# Driver4.net
KiCad netlist of a schematic drawn in Altium Designer
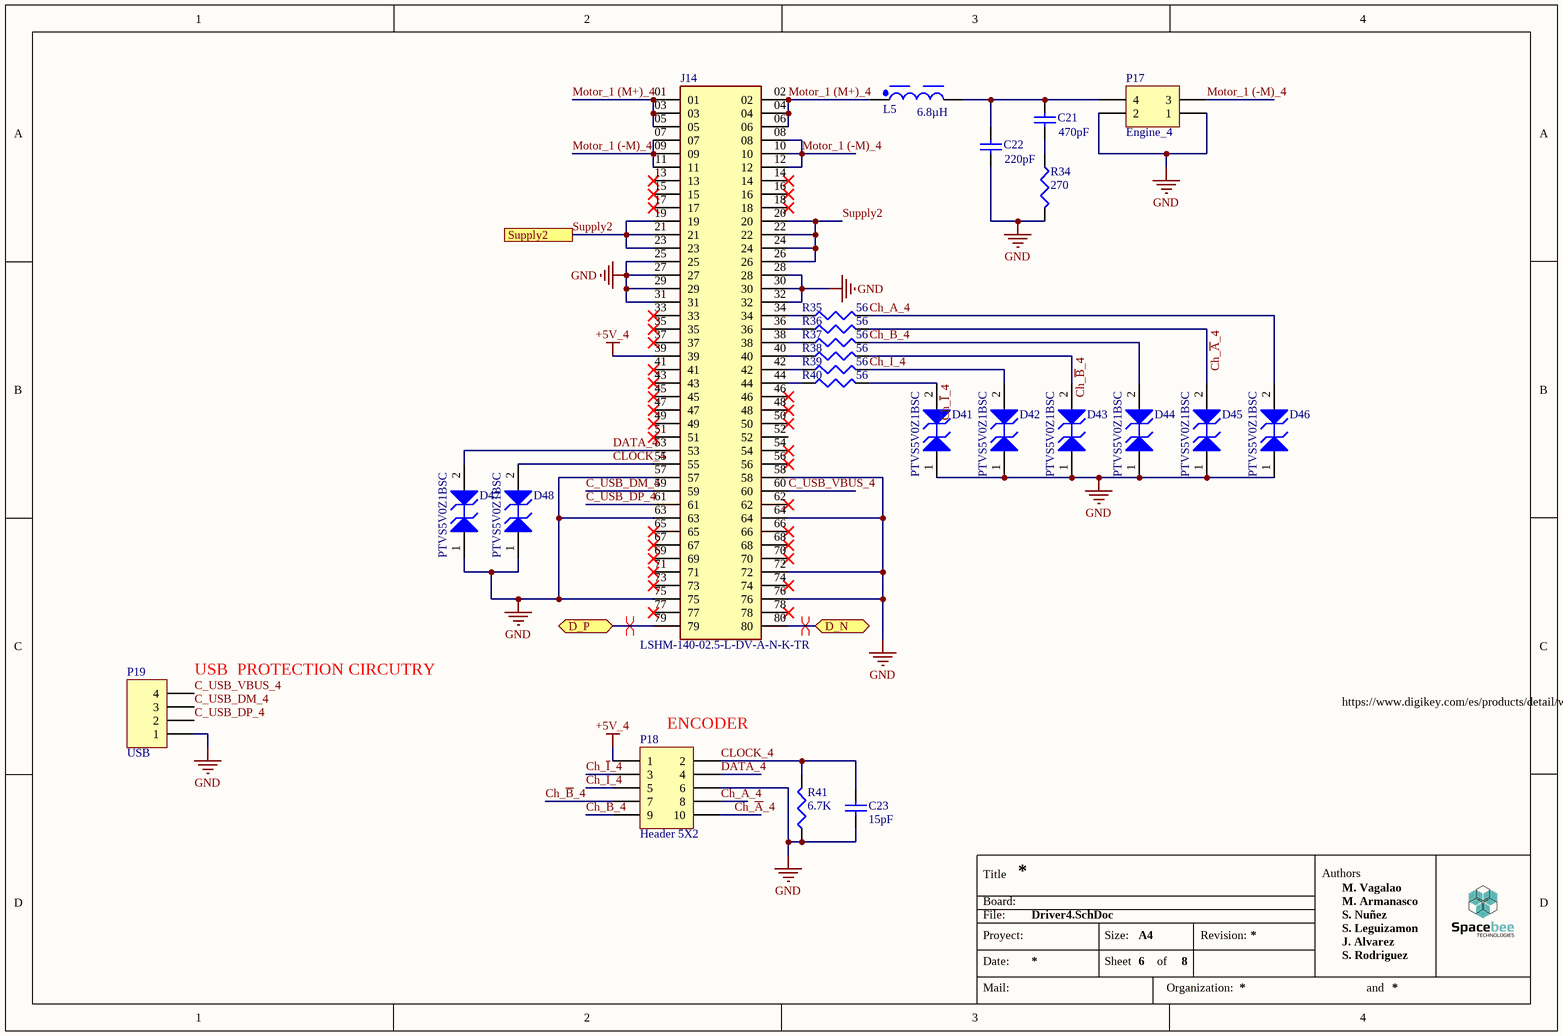
[diagram p0: Driver4.SchDoc]

(export (version "E")
  (design (tool "Eeschema 10.0.6"))
  (components
    (comp (ref "C21")
      (value "470pF")
      (footprint "1608[0603]")
      (description "Capacitor (Semiconductor SIM Model)")
      (fields (field (name "Comment") "Cap Semi") (field (name "PUBLISHER") "Altium Limited"))
      (libsource (lib "Miscellaneous Devices") (part "Cap Semi"))
    )
    (comp (ref "C22")
      (value "220pF")
      (footprint "1608[0603]")
      (description "Capacitor (Semiconductor SIM Model)")
      (fields (field (name "Comment") "Cap Semi") (field (name "PUBLISHER") "Altium Limited"))
      (libsource (lib "Miscellaneous Devices") (part "Cap Semi"))
    )
    (comp (ref "C23")
      (value "15pF")
      (footprint "6-0805_L")
      (description "Capacitor (Semiconductor SIM Model)")
      (fields (field (name "Comment") "Cap Semi") (field (name "PUBLISHER") "Altium Limited"))
      (libsource (lib "SpaceBee") (part "Cap 0805"))
    )
    (comp (ref "D41")
      (value "PTVS5V0Z1BSC")
      (footprint "SOD993B")
      (fields (field (name "MANUFACTURER") "On Semiconductor") (field (name "PARTNUMBER") "1SMB16CAT3"))
      (libsource (lib "DriverLib") (part "PTVS5V0Z1BSC"))
    )
    (comp (ref "D42")
      (value "PTVS5V0Z1BSC")
      (footprint "SOD993B")
      (fields (field (name "MANUFACTURER") "On Semiconductor") (field (name "PARTNUMBER") "1SMB16CAT3"))
      (libsource (lib "DriverLib") (part "PTVS5V0Z1BSC"))
    )
    (comp (ref "D43")
      (value "PTVS5V0Z1BSC")
      (footprint "SOD993B")
      (fields (field (name "MANUFACTURER") "On Semiconductor") (field (name "PARTNUMBER") "1SMB16CAT3"))
      (libsource (lib "DriverLib") (part "PTVS5V0Z1BSC"))
    )
    (comp (ref "D44")
      (value "PTVS5V0Z1BSC")
      (footprint "SOD993B")
      (fields (field (name "MANUFACTURER") "On Semiconductor") (field (name "PARTNUMBER") "1SMB16CAT3"))
      (libsource (lib "DriverLib") (part "PTVS5V0Z1BSC"))
    )
    (comp (ref "D45")
      (value "PTVS5V0Z1BSC")
      (footprint "SOD993B")
      (fields (field (name "MANUFACTURER") "On Semiconductor") (field (name "PARTNUMBER") "1SMB16CAT3"))
      (libsource (lib "DriverLib") (part "PTVS5V0Z1BSC"))
    )
    (comp (ref "D46")
      (value "PTVS5V0Z1BSC")
      (footprint "SOD993B")
      (fields (field (name "MANUFACTURER") "On Semiconductor") (field (name "PARTNUMBER") "1SMB16CAT3"))
      (libsource (lib "DriverLib") (part "PTVS5V0Z1BSC"))
    )
    (comp (ref "D47")
      (value "PTVS5V0Z1BSC")
      (footprint "SOD993B")
      (fields (field (name "MANUFACTURER") "On Semiconductor") (field (name "PARTNUMBER") "1SMB16CAT3"))
      (libsource (lib "DriverLib") (part "PTVS5V0Z1BSC"))
    )
    (comp (ref "D48")
      (value "PTVS5V0Z1BSC")
      (footprint "SOD993B")
      (fields (field (name "MANUFACTURER") "On Semiconductor") (field (name "PARTNUMBER") "1SMB16CAT3"))
      (libsource (lib "DriverLib") (part "PTVS5V0Z1BSC"))
    )
    (comp (ref "J14")
      (value "LSHM-140-02.5-L-DV-A-N-K-TR")
      (footprint "SAMTEC_LSHM-140-02.5-L-DV-A-N-K-TR")
      (description "LSHM - Samtec 0.50mm Razor Beam High-Speed Hermaphroditic Terminal / Socket Strip.")
      (libsource (lib "DriverLib") (part "LSHM-140-02.5-L-DV-A-N-K-TR"))
    )
    (comp (ref "L5")
      (value "6.8µH")
      (footprint "WE-XHMA_6060")
      (description "WE-XHMA SMD Power Inductor, size 1090, 6.8µH, 10.5A, 7.16mΩ")
      (fields
        (field (name "MANUFACTURER PART NUMBER") "78439369068")
        (field (name "MANUFACTURER") "Wurth Elektronik")
      )
      (libsource (lib "DriverLib") (part "78439369068"))
    )
    (comp (ref "P17")
      (value "Engine_4")
      (footprint "MOLEX_1724480004")
      (description "Header, 2-Pin, Dual row")
      (fields (field (name "PUBLISHER") "Altium Limited"))
      (libsource (lib "SpaceBee") (part "Header 2X2"))
    )
    (comp (ref "P18")
      (value "Header 5X2")
      (footprint "CONN_HIF3FC-14PA-2.54DS(71)_HIR")
      (description "Header, 5-Pin, Dual row")
      (fields (field (name "PUBLISHER") "Altium Limited"))
      (libsource (lib "DriverLib") (part "Header 5X2"))
    )
    (comp (ref "P19")
      (value "USB")
      (footprint "Header 4 SMD")
      (description "Header, 4-Pin")
      (fields (field (name "PUBLISHER") "Altium Limited"))
      (libsource (lib "SpaceBee") (part "Header 4 SMD"))
    )
    (comp (ref "R34")
      (value "270")
      (footprint "J1-0603")
      (description "Resistor")
      (fields (field (name "Comment") "Res3") (field (name "PUBLISHER") "Altium Limited"))
      (libsource (lib "Miscellaneous Devices") (part "Res3"))
    )
    (comp (ref "R35")
      (value "56")
      (footprint "J1-0603")
      (description "Resistor")
      (fields (field (name "Comment") "Res3") (field (name "PUBLISHER") "Altium Limited"))
      (libsource (lib "Miscellaneous Devices") (part "Res3"))
    )
    (comp (ref "R36")
      (value "56")
      (footprint "J1-0603")
      (description "Resistor")
      (fields (field (name "Comment") "Res3") (field (name "PUBLISHER") "Altium Limited"))
      (libsource (lib "Miscellaneous Devices") (part "Res3"))
    )
    (comp (ref "R37")
      (value "56")
      (footprint "J1-0603")
      (description "Resistor")
      (fields (field (name "Comment") "Res3") (field (name "PUBLISHER") "Altium Limited"))
      (libsource (lib "Miscellaneous Devices") (part "Res3"))
    )
    (comp (ref "R38")
      (value "56")
      (footprint "J1-0603")
      (description "Resistor")
      (fields (field (name "Comment") "Res3") (field (name "PUBLISHER") "Altium Limited"))
      (libsource (lib "Miscellaneous Devices") (part "Res3"))
    )
    (comp (ref "R39")
      (value "56")
      (footprint "J1-0603")
      (description "Resistor")
      (fields (field (name "Comment") "Res3") (field (name "PUBLISHER") "Altium Limited"))
      (libsource (lib "Miscellaneous Devices") (part "Res3"))
    )
    (comp (ref "R40")
      (value "56")
      (footprint "J1-0603")
      (description "Resistor")
      (fields (field (name "Comment") "Res3") (field (name "PUBLISHER") "Altium Limited"))
      (libsource (lib "Miscellaneous Devices") (part "Res3"))
    )
    (comp (ref "R41")
      (value "6.7K")
      (footprint "J1-0603")
      (description "Resistor")
      (fields (field (name "Comment") "Res3") (field (name "PUBLISHER") "Altium Limited"))
      (libsource (lib "Miscellaneous Devices") (part "Res3"))
    )
  )
  (nets
    (net (code "1") (name "+5V_4") (class "Default")
      (node (ref "J14") (pin "39") (pinfunction "39_39") (pintype "passive"))
      (node (ref "P18") (pin "1") (pinfunction "1_1") (pintype "passive"))
    )
    (net (code "2") (name "/CLOCK_4") (class "Default")
      (node (ref "C23") (pin "2") (pinfunction "2_2") (pintype "passive"))
      (node (ref "D48") (pin "2") (pinfunction "A2_2") (pintype "passive"))
      (node (ref "J14") (pin "55") (pinfunction "55_55") (pintype "passive"))
      (node (ref "P18") (pin "2") (pinfunction "2_2") (pintype "passive"))
      (node (ref "R41") (pin "2") (pinfunction "2_2") (pintype "passive"))
    )
    (net (code "3") (name "/C_USB_DM_4") (class "Default")
      (node (ref "J14") (pin "59") (pinfunction "59_59") (pintype "passive"))
      (node (ref "P19") (pin "3") (pinfunction "3_3") (pintype "passive"))
    )
    (net (code "4") (name "/C_USB_DP_4") (class "Default")
      (node (ref "J14") (pin "61") (pinfunction "61_61") (pintype "passive"))
      (node (ref "P19") (pin "2") (pinfunction "2_2") (pintype "passive"))
    )
    (net (code "5") (name "/C_USB_VBUS_4") (class "Default")
      (node (ref "J14") (pin "60") (pinfunction "60_60") (pintype "passive"))
      (node (ref "P19") (pin "4") (pinfunction "4_4") (pintype "passive"))
    )
    (net (code "6") (name "/Ch_A_4") (class "Default")
      (node (ref "D46") (pin "2") (pinfunction "A2_2") (pintype "passive"))
      (node (ref "P18") (pin "8") (pinfunction "8_8") (pintype "passive"))
      (node (ref "R35") (pin "2") (pinfunction "2_2") (pintype "passive"))
    )
    (net (code "7") (name "/Ch_B_4") (class "Default")
      (node (ref "D44") (pin "2") (pinfunction "A2_2") (pintype "passive"))
      (node (ref "P18") (pin "9") (pinfunction "9_9") (pintype "passive"))
      (node (ref "R37") (pin "2") (pinfunction "2_2") (pintype "passive"))
    )
    (net (code "8") (name "/Ch_I_4") (class "Default")
      (node (ref "D42") (pin "2") (pinfunction "A2_2") (pintype "passive"))
      (node (ref "P18") (pin "5") (pinfunction "5_5") (pintype "passive"))
      (node (ref "R39") (pin "2") (pinfunction "2_2") (pintype "passive"))
    )
    (net (code "9") (name "/Ch_~{A}_4") (class "Default")
      (node (ref "D45") (pin "2") (pinfunction "A2_2") (pintype "passive"))
      (node (ref "P18") (pin "10") (pinfunction "10_10") (pintype "passive"))
      (node (ref "R36") (pin "2") (pinfunction "2_2") (pintype "passive"))
    )
    (net (code "10") (name "/Ch_~{B}_4") (class "Default")
      (node (ref "D43") (pin "2") (pinfunction "A2_2") (pintype "passive"))
      (node (ref "P18") (pin "7") (pinfunction "7_7") (pintype "passive"))
      (node (ref "R38") (pin "2") (pinfunction "2_2") (pintype "passive"))
    )
    (net (code "11") (name "/Ch_~{I}_4") (class "Default")
      (node (ref "D41") (pin "2") (pinfunction "A2_2") (pintype "passive"))
      (node (ref "P18") (pin "3") (pinfunction "3_3") (pintype "passive"))
      (node (ref "R40") (pin "2") (pinfunction "2_2") (pintype "passive"))
    )
    (net (code "12") (name "/DATA_4") (class "Default")
      (node (ref "D47") (pin "2") (pinfunction "A2_2") (pintype "passive"))
      (node (ref "J14") (pin "53") (pinfunction "53_53") (pintype "passive"))
      (node (ref "P18") (pin "4") (pinfunction "4_4") (pintype "passive"))
    )
    (net (code "13") (name "/D_N") (class "Default")
      (node (ref "J14") (pin "80") (pinfunction "80_80") (pintype "passive"))
    )
    (net (code "14") (name "/D_P") (class "Default")
      (node (ref "J14") (pin "79") (pinfunction "79_79") (pintype "passive"))
    )
    (net (code "15") (name "/Motor_1 (-M)_4") (class "Default")
      (node (ref "J14") (pin "07") (pinfunction "07_07") (pintype "passive"))
      (node (ref "J14") (pin "08") (pinfunction "08_08") (pintype "passive"))
      (node (ref "J14") (pin "09") (pinfunction "09_09") (pintype "passive"))
      (node (ref "J14") (pin "10") (pinfunction "10_10") (pintype "passive"))
      (node (ref "J14") (pin "11") (pinfunction "11_11") (pintype "passive"))
      (node (ref "J14") (pin "12") (pinfunction "12_12") (pintype "passive"))
      (node (ref "P17") (pin "3") (pinfunction "3_3") (pintype "passive"))
    )
    (net (code "16") (name "/Motor_1 (M+)_4") (class "Default")
      (node (ref "J14") (pin "01") (pinfunction "01_01") (pintype "passive"))
      (node (ref "J14") (pin "02") (pinfunction "02_02") (pintype "passive"))
      (node (ref "J14") (pin "03") (pinfunction "03_03") (pintype "passive"))
      (node (ref "J14") (pin "04") (pinfunction "04_04") (pintype "passive"))
      (node (ref "J14") (pin "05") (pinfunction "05_05") (pintype "passive"))
      (node (ref "J14") (pin "06") (pinfunction "06_06") (pintype "passive"))
      (node (ref "L5") (pin "1") (pinfunction "1_1") (pintype "passive"))
    )
    (net (code "17") (name "/Supply2") (class "Default")
      (node (ref "J14") (pin "19") (pinfunction "19_19") (pintype "passive"))
      (node (ref "J14") (pin "20") (pinfunction "20_20") (pintype "passive"))
      (node (ref "J14") (pin "21") (pinfunction "21_21") (pintype "passive"))
      (node (ref "J14") (pin "22") (pinfunction "22_22") (pintype "passive"))
      (node (ref "J14") (pin "23") (pinfunction "23_23") (pintype "passive"))
      (node (ref "J14") (pin "24") (pinfunction "24_24") (pintype "passive"))
      (node (ref "J14") (pin "26") (pinfunction "26_26") (pintype "passive"))
    )
    (net (code "18") (name "GND") (class "Default")
      (node (ref "C22") (pin "2") (pinfunction "2_2") (pintype "passive"))
      (node (ref "C23") (pin "1") (pinfunction "1_1") (pintype "passive"))
      (node (ref "D41") (pin "1") (pinfunction "A1_1") (pintype "passive"))
      (node (ref "D42") (pin "1") (pinfunction "A1_1") (pintype "passive"))
      (node (ref "D43") (pin "1") (pinfunction "A1_1") (pintype "passive"))
      (node (ref "D44") (pin "1") (pinfunction "A1_1") (pintype "passive"))
      (node (ref "D45") (pin "1") (pinfunction "A1_1") (pintype "passive"))
      (node (ref "D46") (pin "1") (pinfunction "A1_1") (pintype "passive"))
      (node (ref "D47") (pin "1") (pinfunction "A1_1") (pintype "passive"))
      (node (ref "D48") (pin "1") (pinfunction "A1_1") (pintype "passive"))
      (node (ref "J14") (pin "25") (pinfunction "25_25") (pintype "passive"))
      (node (ref "J14") (pin "27") (pinfunction "27_27") (pintype "passive"))
      (node (ref "J14") (pin "28") (pinfunction "28_28") (pintype "passive"))
      (node (ref "J14") (pin "29") (pinfunction "29_29") (pintype "passive"))
      (node (ref "J14") (pin "30") (pinfunction "30_30") (pintype "passive"))
      (node (ref "J14") (pin "31") (pinfunction "31_31") (pintype "passive"))
      (node (ref "J14") (pin "32") (pinfunction "32_32") (pintype "passive"))
      (node (ref "J14") (pin "57") (pinfunction "57_57") (pintype "passive"))
      (node (ref "J14") (pin "58") (pinfunction "58_58") (pintype "passive"))
      (node (ref "J14") (pin "63") (pinfunction "63_63") (pintype "passive"))
      (node (ref "J14") (pin "64") (pinfunction "64_64") (pintype "passive"))
      (node (ref "J14") (pin "72") (pinfunction "72_72") (pintype "passive"))
      (node (ref "J14") (pin "75") (pinfunction "75_75") (pintype "passive"))
      (node (ref "J14") (pin "76") (pinfunction "76_76") (pintype "passive"))
      (node (ref "P17") (pin "1") (pinfunction "1_1") (pintype "passive"))
      (node (ref "P17") (pin "2") (pinfunction "2_2") (pintype "passive"))
      (node (ref "P18") (pin "6") (pinfunction "6_6") (pintype "passive"))
      (node (ref "P19") (pin "1") (pinfunction "1_1") (pintype "passive"))
      (node (ref "R34") (pin "2") (pinfunction "2_2") (pintype "passive"))
      (node (ref "R41") (pin "1") (pinfunction "1_1") (pintype "passive"))
    )
    (net (code "19") (name "Net-(C21-Pad1)") (class "Default")
      (node (ref "C21") (pin "1") (pinfunction "1_1") (pintype "passive"))
      (node (ref "C22") (pin "1") (pinfunction "1_1") (pintype "passive"))
      (node (ref "L5") (pin "2") (pinfunction "2_2") (pintype "passive"))
      (node (ref "P17") (pin "4") (pinfunction "4_4") (pintype "passive"))
    )
    (net (code "20") (name "Net-(C21-Pad2)") (class "Default")
      (node (ref "C21") (pin "2") (pinfunction "2_2") (pintype "passive"))
      (node (ref "R34") (pin "1") (pinfunction "1_1") (pintype "passive"))
    )
    (net (code "21") (name "Net-(J14-Pad34)") (class "Default")
      (node (ref "J14") (pin "34") (pinfunction "34_34") (pintype "passive"))
      (node (ref "R35") (pin "1") (pinfunction "1_1") (pintype "passive"))
    )
    (net (code "22") (name "Net-(J14-Pad36)") (class "Default")
      (node (ref "J14") (pin "36") (pinfunction "36_36") (pintype "passive"))
      (node (ref "R36") (pin "1") (pinfunction "1_1") (pintype "passive"))
    )
    (net (code "23") (name "Net-(J14-Pad38)") (class "Default")
      (node (ref "J14") (pin "38") (pinfunction "38_38") (pintype "passive"))
      (node (ref "R37") (pin "1") (pinfunction "1_1") (pintype "passive"))
    )
    (net (code "24") (name "Net-(J14-Pad40)") (class "Default")
      (node (ref "J14") (pin "40") (pinfunction "40_40") (pintype "passive"))
      (node (ref "R38") (pin "1") (pinfunction "1_1") (pintype "passive"))
    )
    (net (code "25") (name "Net-(J14-Pad42)") (class "Default")
      (node (ref "J14") (pin "42") (pinfunction "42_42") (pintype "passive"))
      (node (ref "R39") (pin "1") (pinfunction "1_1") (pintype "passive"))
    )
    (net (code "26") (name "Net-(J14-Pad44)") (class "Default")
      (node (ref "J14") (pin "44") (pinfunction "44_44") (pintype "passive"))
      (node (ref "R40") (pin "1") (pinfunction "1_1") (pintype "passive"))
    )
    (net (code "27") (name "unconnected-(J14-Pad13)") (class "Default")
      (node (ref "J14") (pin "13") (pinfunction "13_13") (pintype "passive+no_connect"))
    )
    (net (code "28") (name "unconnected-(J14-Pad14)") (class "Default")
      (node (ref "J14") (pin "14") (pinfunction "14_14") (pintype "passive+no_connect"))
    )
    (net (code "29") (name "unconnected-(J14-Pad15)") (class "Default")
      (node (ref "J14") (pin "15") (pinfunction "15_15") (pintype "passive+no_connect"))
    )
    (net (code "30") (name "unconnected-(J14-Pad16)") (class "Default")
      (node (ref "J14") (pin "16") (pinfunction "16_16") (pintype "passive+no_connect"))
    )
    (net (code "31") (name "unconnected-(J14-Pad17)") (class "Default")
      (node (ref "J14") (pin "17") (pinfunction "17_17") (pintype "passive+no_connect"))
    )
    (net (code "32") (name "unconnected-(J14-Pad18)") (class "Default")
      (node (ref "J14") (pin "18") (pinfunction "18_18") (pintype "passive+no_connect"))
    )
    (net (code "33") (name "unconnected-(J14-Pad33)") (class "Default")
      (node (ref "J14") (pin "33") (pinfunction "33_33") (pintype "passive+no_connect"))
    )
    (net (code "34") (name "unconnected-(J14-Pad35)") (class "Default")
      (node (ref "J14") (pin "35") (pinfunction "35_35") (pintype "passive+no_connect"))
    )
    (net (code "35") (name "unconnected-(J14-Pad37)") (class "Default")
      (node (ref "J14") (pin "37") (pinfunction "37_37") (pintype "passive+no_connect"))
    )
    (net (code "36") (name "unconnected-(J14-Pad41)") (class "Default")
      (node (ref "J14") (pin "41") (pinfunction "41_41") (pintype "passive+no_connect"))
    )
    (net (code "37") (name "unconnected-(J14-Pad43)") (class "Default")
      (node (ref "J14") (pin "43") (pinfunction "43_43") (pintype "passive+no_connect"))
    )
    (net (code "38") (name "unconnected-(J14-Pad45)") (class "Default")
      (node (ref "J14") (pin "45") (pinfunction "45_45") (pintype "passive+no_connect"))
    )
    (net (code "39") (name "unconnected-(J14-Pad46)") (class "Default")
      (node (ref "J14") (pin "46") (pinfunction "46_46") (pintype "passive+no_connect"))
    )
    (net (code "40") (name "unconnected-(J14-Pad47)") (class "Default")
      (node (ref "J14") (pin "47") (pinfunction "47_47") (pintype "passive+no_connect"))
    )
    (net (code "41") (name "unconnected-(J14-Pad48)") (class "Default")
      (node (ref "J14") (pin "48") (pinfunction "48_48") (pintype "passive+no_connect"))
    )
    (net (code "42") (name "unconnected-(J14-Pad49)") (class "Default")
      (node (ref "J14") (pin "49") (pinfunction "49_49") (pintype "passive+no_connect"))
    )
    (net (code "43") (name "unconnected-(J14-Pad50)") (class "Default")
      (node (ref "J14") (pin "50") (pinfunction "50_50") (pintype "passive+no_connect"))
    )
    (net (code "44") (name "unconnected-(J14-Pad51)") (class "Default")
      (node (ref "J14") (pin "51") (pinfunction "51_51") (pintype "passive+no_connect"))
    )
    (net (code "45") (name "unconnected-(J14-Pad52)") (class "Default")
      (node (ref "J14") (pin "52") (pinfunction "52_52") (pintype "passive"))
    )
    (net (code "46") (name "unconnected-(J14-Pad54)") (class "Default")
      (node (ref "J14") (pin "54") (pinfunction "54_54") (pintype "passive+no_connect"))
    )
    (net (code "47") (name "unconnected-(J14-Pad56)") (class "Default")
      (node (ref "J14") (pin "56") (pinfunction "56_56") (pintype "passive+no_connect"))
    )
    (net (code "48") (name "unconnected-(J14-Pad62)") (class "Default")
      (node (ref "J14") (pin "62") (pinfunction "62_62") (pintype "passive+no_connect"))
    )
    (net (code "49") (name "unconnected-(J14-Pad65)") (class "Default")
      (node (ref "J14") (pin "65") (pinfunction "65_65") (pintype "passive+no_connect"))
    )
    (net (code "50") (name "unconnected-(J14-Pad66)") (class "Default")
      (node (ref "J14") (pin "66") (pinfunction "66_66") (pintype "passive+no_connect"))
    )
    (net (code "51") (name "unconnected-(J14-Pad67)") (class "Default")
      (node (ref "J14") (pin "67") (pinfunction "67_67") (pintype "passive+no_connect"))
    )
    (net (code "52") (name "unconnected-(J14-Pad68)") (class "Default")
      (node (ref "J14") (pin "68") (pinfunction "68_68") (pintype "passive+no_connect"))
    )
    (net (code "53") (name "unconnected-(J14-Pad69)") (class "Default")
      (node (ref "J14") (pin "69") (pinfunction "69_69") (pintype "passive+no_connect"))
    )
    (net (code "54") (name "unconnected-(J14-Pad70)") (class "Default")
      (node (ref "J14") (pin "70") (pinfunction "70_70") (pintype "passive+no_connect"))
    )
    (net (code "55") (name "unconnected-(J14-Pad71)") (class "Default")
      (node (ref "J14") (pin "71") (pinfunction "71_71") (pintype "passive+no_connect"))
    )
    (net (code "56") (name "unconnected-(J14-Pad73)") (class "Default")
      (node (ref "J14") (pin "73") (pinfunction "73_73") (pintype "passive+no_connect"))
    )
    (net (code "57") (name "unconnected-(J14-Pad74)") (class "Default")
      (node (ref "J14") (pin "74") (pinfunction "74_74") (pintype "passive+no_connect"))
    )
    (net (code "58") (name "unconnected-(J14-Pad77)") (class "Default")
      (node (ref "J14") (pin "77") (pinfunction "77_77") (pintype "passive+no_connect"))
    )
    (net (code "59") (name "unconnected-(J14-Pad78)") (class "Default")
      (node (ref "J14") (pin "78") (pinfunction "78_78") (pintype "passive+no_connect"))
    )
  )
)
